# Tiva_C_Base.net
KiCad netlist of a schematic drawn in Altium Designer
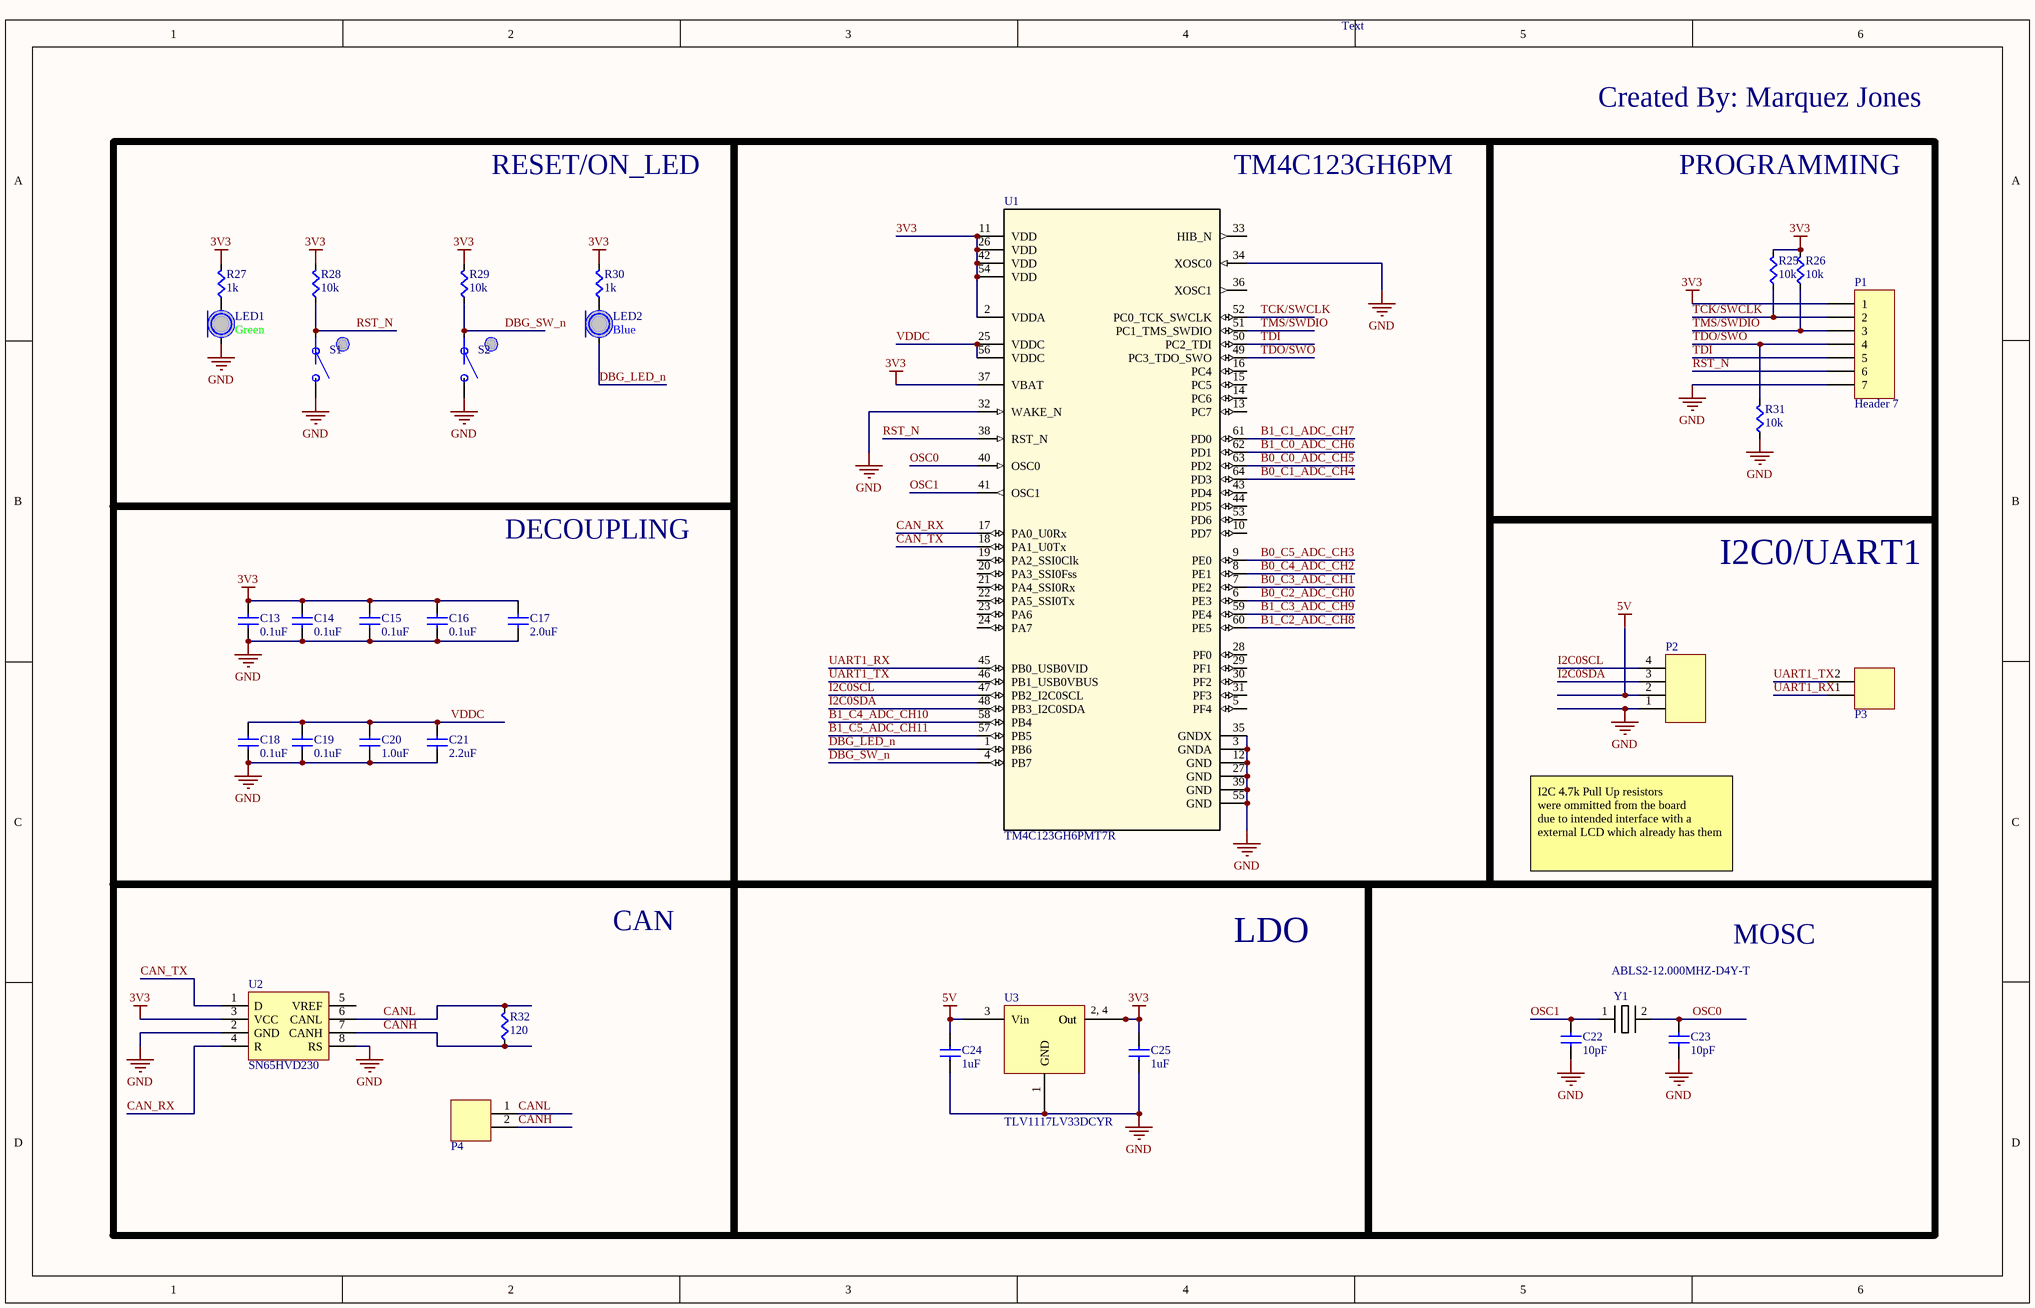
[diagram p0: Tiva_C_Base.SchDoc]

(export (version "E")
  (design (tool "Eeschema 10.0.6"))
  (components
    (comp (ref "C13")
      (value "0.1uF")
      (footprint "CAPC0603")
      (fields (field (name "Comment") "Cap"))
      (libsource (lib "SubjuGator8") (part "Cap"))
    )
    (comp (ref "C14")
      (value "0.1uF")
      (footprint "CAPC0603")
      (fields (field (name "Comment") "Cap"))
      (libsource (lib "SubjuGator8") (part "Cap"))
    )
    (comp (ref "C15")
      (value "0.1uF")
      (footprint "CAPC0603")
      (fields (field (name "Comment") "Cap"))
      (libsource (lib "SubjuGator8") (part "Cap"))
    )
    (comp (ref "C16")
      (value "0.1uF")
      (footprint "CAPC0603")
      (fields (field (name "Comment") "Cap"))
      (libsource (lib "SubjuGator8") (part "Cap"))
    )
    (comp (ref "C17")
      (value "2.0uF")
      (footprint "CAPC0603")
      (fields (field (name "Comment") "Cap"))
      (libsource (lib "SubjuGator8") (part "Cap"))
    )
    (comp (ref "C18")
      (value "0.1uF")
      (footprint "CAPC0603")
      (fields (field (name "Comment") "Cap"))
      (libsource (lib "SubjuGator8") (part "Cap"))
    )
    (comp (ref "C19")
      (value "0.1uF")
      (footprint "CAPC0603")
      (fields (field (name "Comment") "Cap"))
      (libsource (lib "SubjuGator8") (part "Cap"))
    )
    (comp (ref "C20")
      (value "1.0uF")
      (footprint "CAPC0603")
      (fields (field (name "Comment") "Cap"))
      (libsource (lib "SubjuGator8") (part "Cap"))
    )
    (comp (ref "C21")
      (value "2.2uF")
      (footprint "CAPC0603")
      (fields (field (name "Comment") "Cap"))
      (libsource (lib "SubjuGator8") (part "Cap"))
    )
    (comp (ref "C22")
      (value "10pF")
      (footprint "CAPC0603")
      (fields (field (name "Comment") "Cap"))
      (libsource (lib "Passives") (part "Cap"))
    )
    (comp (ref "C23")
      (value "10pF")
      (footprint "CAPC0603")
      (fields (field (name "Comment") "Cap"))
      (libsource (lib "Passives") (part "Cap"))
    )
    (comp (ref "C24")
      (value "1uF")
      (footprint "CAPC0603")
      (fields (field (name "MANUFACTURER PART NUMBER") "C0603C105K8PACTU") (field (name "Comment") "Cap"))
      (libsource (lib "SubjuGator8") (part "Cap"))
    )
    (comp (ref "C25")
      (value "1uF")
      (footprint "CAPC0603")
      (fields (field (name "MANUFACTURER PART NUMBER") "C0603C105K8PACTU") (field (name "Comment") "Cap"))
      (libsource (lib "SubjuGator8") (part "Cap"))
    )
    (comp (ref "LED1")
      (value "LED")
      (footprint "LED0603")
      (fields (field (name "COLOR") "Green"))
      (libsource (lib "SubjuGator8") (part "LED"))
    )
    (comp (ref "LED2")
      (value "LED")
      (footprint "LED0603")
      (fields (field (name "COLOR") "Blue"))
      (libsource (lib "SubjuGator8") (part "LED"))
    )
    (comp (ref "P1")
      (value "Header 7")
      (footprint "HDR1X7")
      (description "Header, 7-Pin")
      (fields (field (name "PUBLISHER") "Altium Limited"))
      (libsource (lib "Miscellaneous Connectors") (part "Header 7"))
    )
    (comp (ref "P2")
      (value "~")
      (footprint "MOLEX-HDR-1X4-SHERLOCK-VERT")
      (libsource (lib "SubjuGator8") (part "MOLEX-HDR-1x4-SHERLOCK_VERT"))
    )
    (comp (ref "P3")
      (value "2-pin Vert Sherlock")
      (footprint "MOLEX-HDR-1X2-SHERLOCK-VERT")
      (libsource (lib "SubjuGator8") (part "MOLEX-HDR-1x2-SHERLOCK_VERT"))
    )
    (comp (ref "P4")
      (value "2-pin Vert Sherlock")
      (footprint "MOLEX-HDR-1X2-SHERLOCK-VERT")
      (libsource (lib "") (part "MOLEX-HDR-1x2-SHERLOCK_VERT_1"))
    )
    (comp (ref "R25")
      (value "10k")
      (footprint "RES0603")
      (fields (field (name "Comment") "Res"))
      (libsource (lib "SubjuGator8") (part "Res"))
    )
    (comp (ref "R26")
      (value "10k")
      (footprint "RES0603")
      (fields (field (name "Comment") "Res"))
      (libsource (lib "SubjuGator8") (part "Res"))
    )
    (comp (ref "R27")
      (value "1k")
      (footprint "RES0603")
      (fields (field (name "Comment") "Res"))
      (libsource (lib "SubjuGator8") (part "Res"))
    )
    (comp (ref "R28")
      (value "10k")
      (footprint "RES0603")
      (fields (field (name "Comment") "Res"))
      (libsource (lib "SubjuGator8") (part "Res"))
    )
    (comp (ref "R29")
      (value "10k")
      (footprint "RES0603")
      (fields (field (name "Comment") "Res"))
      (libsource (lib "SubjuGator8") (part "Res"))
    )
    (comp (ref "R30")
      (value "1k")
      (footprint "RES0603")
      (fields (field (name "Comment") "Res"))
      (libsource (lib "SubjuGator8") (part "Res"))
    )
    (comp (ref "R31")
      (value "10k")
      (footprint "RES0603")
      (fields (field (name "Comment") "Res"))
      (libsource (lib "SubjuGator8") (part "Res"))
    )
    (comp (ref "R32")
      (value "120")
      (footprint "RES0603")
      (fields (field (name "Comment") "Res"))
      (libsource (lib "SubjuGator8") (part "Res"))
    )
    (comp (ref "S1")
      (value "Button")
      (footprint "PTS645xxxxSMTR92")
      (description "SPST Button")
      (libsource (lib "SubjuGator8") (part "Button"))
    )
    (comp (ref "S2")
      (value "Button")
      (footprint "PTS645xxxxSMTR92")
      (description "SPST Button")
      (libsource (lib "SubjuGator8") (part "Button"))
    )
    (comp (ref "U1")
      (value "TM4C123GH6PMT7R")
      (footprint "TM4C123GH6PMT7R_L")
      (description "Imported")
      (fields
        (field (name "PARTNUMBER") "TM4C123GH6PMTR")
        (field (name "ALTERNATE_PARTNUMBER") "TM4C123GH6PMT")
      )
      (libsource (lib "SubjuGator8") (part "TM4C123GH6PMT7R"))
    )
    (comp (ref "U2")
      (value "SN65HVD230")
      (footprint "SOIC-8pin")
      (description "3.3V CAN Bus Transceiver")
      (libsource (lib "SubjuGator8") (part "SN65HVD230"))
    )
    (comp (ref "U3")
      (value "TLV1117LV33DCYR")
      (footprint "SOT23-4N")
      (description "IC REG LINEAR 3.3V 1A SOT223-4")
      (fields (field (name "DIGI-KEY PART NUMBER") "296-28778-1-ND"))
      (libsource (lib "ICs") (part "TLV1117LV33DCYR"))
    )
    (comp (ref "Y1")
      (value "ABLS2-12.000MHZ-D4Y-T")
      (footprint "HC49/US")
      (description "12MHz ±30ppm Crystal 18pF 50 Ohm -40°C ~ 85°C Surface Mount HC49/US")
      (libsource (lib "SubjuGator8") (part "ABLS2-12.000MHZ-D4Y-T"))
    )
  )
  (nets
    (net (code "1") (name "/B0_C0_ADC_CH5") (class "Default")
      (node (ref "U1") (pin "63") (pinfunction "PD2_63") (pintype "bidirectional"))
    )
    (net (code "2") (name "/B0_C1_ADC_CH4") (class "Default")
      (node (ref "U1") (pin "64") (pinfunction "PD3_64") (pintype "bidirectional"))
    )
    (net (code "3") (name "/B0_C2_ADC_CH0") (class "Default")
      (node (ref "U1") (pin "6") (pinfunction "PE3_6") (pintype "bidirectional"))
    )
    (net (code "4") (name "/B0_C3_ADC_CH1") (class "Default")
      (node (ref "U1") (pin "7") (pinfunction "PE2_7") (pintype "bidirectional"))
    )
    (net (code "5") (name "/B0_C4_ADC_CH2") (class "Default")
      (node (ref "U1") (pin "8") (pinfunction "PE1_8") (pintype "bidirectional"))
    )
    (net (code "6") (name "/B0_C5_ADC_CH3") (class "Default")
      (node (ref "U1") (pin "9") (pinfunction "PE0_9") (pintype "bidirectional"))
    )
    (net (code "7") (name "/B1_C0_ADC_CH6") (class "Default")
      (node (ref "U1") (pin "62") (pinfunction "PD1_62") (pintype "bidirectional"))
    )
    (net (code "8") (name "/B1_C1_ADC_CH7") (class "Default")
      (node (ref "U1") (pin "61") (pinfunction "PD0_61") (pintype "bidirectional"))
    )
    (net (code "9") (name "/B1_C2_ADC_CH8") (class "Default")
      (node (ref "U1") (pin "60") (pinfunction "PE5_60") (pintype "bidirectional"))
    )
    (net (code "10") (name "/B1_C3_ADC_CH9") (class "Default")
      (node (ref "U1") (pin "59") (pinfunction "PE4_59") (pintype "bidirectional"))
    )
    (net (code "11") (name "/B1_C4_ADC_CH10") (class "Default")
      (node (ref "U1") (pin "58") (pinfunction "PB4_58") (pintype "bidirectional"))
    )
    (net (code "12") (name "/B1_C5_ADC_CH11") (class "Default")
      (node (ref "U1") (pin "57") (pinfunction "PB5_57") (pintype "bidirectional"))
    )
    (net (code "13") (name "/CANH") (class "Default")
      (node (ref "P4") (pin "2") (pinfunction "2_2") (pintype "passive"))
      (node (ref "R32") (pin "2") (pinfunction "B_2") (pintype "passive"))
      (node (ref "U2") (pin "7") (pinfunction "CANH_7") (pintype "passive"))
    )
    (net (code "14") (name "/CANL") (class "Default")
      (node (ref "P4") (pin "1") (pinfunction "1_1") (pintype "passive"))
      (node (ref "R32") (pin "1") (pinfunction "A_1") (pintype "passive"))
      (node (ref "U2") (pin "6") (pinfunction "CANL_6") (pintype "passive"))
    )
    (net (code "15") (name "/CAN_RX") (class "Default")
      (node (ref "U1") (pin "17") (pinfunction "PA0_U0Rx_17") (pintype "bidirectional"))
      (node (ref "U2") (pin "4") (pinfunction "R_4") (pintype "passive"))
    )
    (net (code "16") (name "/CAN_TX") (class "Default")
      (node (ref "U1") (pin "18") (pinfunction "PA1_U0Tx_18") (pintype "bidirectional"))
      (node (ref "U2") (pin "1") (pinfunction "D_1") (pintype "passive"))
    )
    (net (code "17") (name "/DBG_LED_n") (class "Default")
      (node (ref "LED2") (pin "C") (pinfunction "C_C") (pintype "passive"))
      (node (ref "U1") (pin "1") (pinfunction "PB6_1") (pintype "bidirectional"))
    )
    (net (code "18") (name "/DBG_SW_n") (class "Default")
      (node (ref "R29") (pin "2") (pinfunction "B_2") (pintype "passive"))
      (node (ref "S2") (pin "A") (pinfunction "A_A") (pintype "passive"))
      (node (ref "U1") (pin "4") (pinfunction "PB7_4") (pintype "bidirectional"))
    )
    (net (code "19") (name "/I2C0SCL") (class "Default")
      (node (ref "P2") (pin "4") (pinfunction "4_4") (pintype "passive"))
      (node (ref "U1") (pin "47") (pinfunction "PB2_I2C0SCL_47") (pintype "bidirectional"))
    )
    (net (code "20") (name "/I2C0SDA") (class "Default")
      (node (ref "P2") (pin "3") (pinfunction "3_3") (pintype "passive"))
      (node (ref "U1") (pin "48") (pinfunction "PB3_I2C0SDA_48") (pintype "bidirectional"))
    )
    (net (code "21") (name "/OSC0") (class "Default")
      (node (ref "C23") (pin "1") (pinfunction "A_1") (pintype "passive"))
      (node (ref "U1") (pin "40") (pinfunction "OSC0_40") (pintype "input"))
      (node (ref "Y1") (pin "2") (pinfunction "2_2") (pintype "passive"))
    )
    (net (code "22") (name "/OSC1") (class "Default")
      (node (ref "C22") (pin "1") (pinfunction "A_1") (pintype "passive"))
      (node (ref "U1") (pin "41") (pinfunction "OSC1_41") (pintype "output"))
      (node (ref "Y1") (pin "1") (pinfunction "1_1") (pintype "passive"))
    )
    (net (code "23") (name "/RST_N") (class "Default")
      (node (ref "P1") (pin "6") (pinfunction "6_6") (pintype "passive"))
      (node (ref "R28") (pin "2") (pinfunction "B_2") (pintype "passive"))
      (node (ref "S1") (pin "A") (pinfunction "A_A") (pintype "passive"))
      (node (ref "U1") (pin "38") (pinfunction "RST_N_38") (pintype "input"))
    )
    (net (code "24") (name "/TCK{slash}SWCLK") (class "Default")
      (node (ref "P1") (pin "2") (pinfunction "2_2") (pintype "passive"))
      (node (ref "R25") (pin "2") (pinfunction "B_2") (pintype "passive"))
      (node (ref "U1") (pin "52") (pinfunction "PC0_TCK_SWCLK_52") (pintype "bidirectional"))
    )
    (net (code "25") (name "/TDI") (class "Default")
      (node (ref "P1") (pin "5") (pinfunction "5_5") (pintype "passive"))
      (node (ref "U1") (pin "50") (pinfunction "PC2_TDI_50") (pintype "bidirectional"))
    )
    (net (code "26") (name "/TDO{slash}SWO") (class "Default")
      (node (ref "P1") (pin "4") (pinfunction "4_4") (pintype "passive"))
      (node (ref "R31") (pin "1") (pinfunction "A_1") (pintype "passive"))
      (node (ref "U1") (pin "49") (pinfunction "PC3_TDO_SWO_49") (pintype "bidirectional"))
    )
    (net (code "27") (name "/TMS{slash}SWDIO") (class "Default")
      (node (ref "P1") (pin "3") (pinfunction "3_3") (pintype "passive"))
      (node (ref "R26") (pin "2") (pinfunction "B_2") (pintype "passive"))
      (node (ref "U1") (pin "51") (pinfunction "PC1_TMS_SWDIO_51") (pintype "bidirectional"))
    )
    (net (code "28") (name "/UART1_RX") (class "Default")
      (node (ref "P3") (pin "1") (pinfunction "1_1") (pintype "passive"))
      (node (ref "U1") (pin "45") (pinfunction "PB0_USB0VID_45") (pintype "bidirectional"))
    )
    (net (code "29") (name "/UART1_TX") (class "Default")
      (node (ref "P3") (pin "2") (pinfunction "2_2") (pintype "passive"))
      (node (ref "U1") (pin "46") (pinfunction "PB1_USB0VBUS_46") (pintype "bidirectional"))
    )
    (net (code "30") (name "/VDDC") (class "Default")
      (node (ref "C18") (pin "1") (pinfunction "A_1") (pintype "passive"))
      (node (ref "C19") (pin "1") (pinfunction "A_1") (pintype "passive"))
      (node (ref "C20") (pin "1") (pinfunction "A_1") (pintype "passive"))
      (node (ref "C21") (pin "1") (pinfunction "A_1") (pintype "passive"))
      (node (ref "U1") (pin "25") (pinfunction "VDDC_25") (pintype "power_in"))
      (node (ref "U1") (pin "56") (pinfunction "VDDC_56") (pintype "power_in"))
    )
    (net (code "31") (name "3V3") (class "Default")
      (node (ref "C13") (pin "1") (pinfunction "A_1") (pintype "passive"))
      (node (ref "C14") (pin "1") (pinfunction "A_1") (pintype "passive"))
      (node (ref "C15") (pin "1") (pinfunction "A_1") (pintype "passive"))
      (node (ref "C16") (pin "1") (pinfunction "A_1") (pintype "passive"))
      (node (ref "C17") (pin "1") (pinfunction "A_1") (pintype "passive"))
      (node (ref "C25") (pin "1") (pinfunction "A_1") (pintype "passive"))
      (node (ref "P1") (pin "1") (pinfunction "1_1") (pintype "passive"))
      (node (ref "R25") (pin "1") (pinfunction "A_1") (pintype "passive"))
      (node (ref "R26") (pin "1") (pinfunction "A_1") (pintype "passive"))
      (node (ref "R27") (pin "1") (pinfunction "A_1") (pintype "passive"))
      (node (ref "R28") (pin "1") (pinfunction "A_1") (pintype "passive"))
      (node (ref "R29") (pin "1") (pinfunction "A_1") (pintype "passive"))
      (node (ref "R30") (pin "1") (pinfunction "A_1") (pintype "passive"))
      (node (ref "U1") (pin "11") (pinfunction "VDD_11") (pintype "power_in"))
      (node (ref "U1") (pin "2") (pinfunction "VDDA_2") (pintype "power_in"))
      (node (ref "U1") (pin "26") (pinfunction "VDD_26") (pintype "power_in"))
      (node (ref "U1") (pin "37") (pinfunction "VBAT_37") (pintype "power_in"))
      (node (ref "U1") (pin "42") (pinfunction "VDD_42") (pintype "power_in"))
      (node (ref "U1") (pin "54") (pinfunction "VDD_54") (pintype "power_in"))
      (node (ref "U2") (pin "3") (pinfunction "VCC_3") (pintype "passive"))
      (node (ref "U3") (pin "2") (pinfunction "Out_2") (pintype "passive"))
      (node (ref "U3") (pin "4") (pinfunction "Out_4") (pintype "passive"))
    )
    (net (code "32") (name "5V") (class "Default")
      (node (ref "C24") (pin "1") (pinfunction "A_1") (pintype "passive"))
      (node (ref "P2") (pin "2") (pinfunction "2_2") (pintype "passive"))
      (node (ref "U3") (pin "3") (pinfunction "Vin_3") (pintype "passive"))
    )
    (net (code "33") (name "GND") (class "Default")
      (node (ref "C13") (pin "2") (pinfunction "B_2") (pintype "passive"))
      (node (ref "C14") (pin "2") (pinfunction "B_2") (pintype "passive"))
      (node (ref "C15") (pin "2") (pinfunction "B_2") (pintype "passive"))
      (node (ref "C16") (pin "2") (pinfunction "B_2") (pintype "passive"))
      (node (ref "C17") (pin "2") (pinfunction "B_2") (pintype "passive"))
      (node (ref "C18") (pin "2") (pinfunction "B_2") (pintype "passive"))
      (node (ref "C19") (pin "2") (pinfunction "B_2") (pintype "passive"))
      (node (ref "C20") (pin "2") (pinfunction "B_2") (pintype "passive"))
      (node (ref "C21") (pin "2") (pinfunction "B_2") (pintype "passive"))
      (node (ref "C22") (pin "2") (pinfunction "B_2") (pintype "passive"))
      (node (ref "C23") (pin "2") (pinfunction "B_2") (pintype "passive"))
      (node (ref "C24") (pin "2") (pinfunction "B_2") (pintype "passive"))
      (node (ref "C25") (pin "2") (pinfunction "B_2") (pintype "passive"))
      (node (ref "LED1") (pin "C") (pinfunction "C_C") (pintype "passive"))
      (node (ref "P1") (pin "7") (pinfunction "7_7") (pintype "passive"))
      (node (ref "P2") (pin "1") (pinfunction "1_1") (pintype "passive"))
      (node (ref "R31") (pin "2") (pinfunction "B_2") (pintype "passive"))
      (node (ref "S1") (pin "B") (pinfunction "B_B") (pintype "passive"))
      (node (ref "S2") (pin "B") (pinfunction "B_B") (pintype "passive"))
      (node (ref "U1") (pin "12") (pinfunction "GND_12") (pintype "power_in"))
      (node (ref "U1") (pin "27") (pinfunction "GND_27") (pintype "power_in"))
      (node (ref "U1") (pin "3") (pinfunction "GNDA_3") (pintype "power_in"))
      (node (ref "U1") (pin "32") (pinfunction "WAKE_N_32") (pintype "input"))
      (node (ref "U1") (pin "34") (pinfunction "XOSC0_34") (pintype "input"))
      (node (ref "U1") (pin "35") (pinfunction "GNDX_35") (pintype "power_in"))
      (node (ref "U1") (pin "39") (pinfunction "GND_39") (pintype "power_in"))
      (node (ref "U1") (pin "55") (pinfunction "GND_55") (pintype "power_in"))
      (node (ref "U2") (pin "2") (pinfunction "GND_2") (pintype "passive"))
      (node (ref "U2") (pin "8") (pinfunction "RS_8") (pintype "passive"))
      (node (ref "U3") (pin "1") (pinfunction "GND_1") (pintype "passive"))
    )
    (net (code "34") (name "Net-(R27-B)") (class "Default")
      (node (ref "LED1") (pin "A") (pinfunction "A_A") (pintype "passive"))
      (node (ref "R27") (pin "2") (pinfunction "B_2") (pintype "passive"))
    )
    (net (code "35") (name "Net-(R30-B)") (class "Default")
      (node (ref "LED2") (pin "A") (pinfunction "A_A") (pintype "passive"))
      (node (ref "R30") (pin "2") (pinfunction "B_2") (pintype "passive"))
    )
    (net (code "36") (name "unconnected-(U1-HIB_N-Pad33)") (class "Default")
      (node (ref "U1") (pin "33") (pinfunction "HIB_N_33") (pintype "output"))
    )
    (net (code "37") (name "unconnected-(U1-PA2_SSI0Clk-Pad19)") (class "Default")
      (node (ref "U1") (pin "19") (pinfunction "PA2_SSI0Clk_19") (pintype "bidirectional"))
    )
    (net (code "38") (name "unconnected-(U1-PA3_SSI0Fss-Pad20)") (class "Default")
      (node (ref "U1") (pin "20") (pinfunction "PA3_SSI0Fss_20") (pintype "bidirectional"))
    )
    (net (code "39") (name "unconnected-(U1-PA4_SSI0Rx-Pad21)") (class "Default")
      (node (ref "U1") (pin "21") (pinfunction "PA4_SSI0Rx_21") (pintype "bidirectional"))
    )
    (net (code "40") (name "unconnected-(U1-PA5_SSI0Tx-Pad22)") (class "Default")
      (node (ref "U1") (pin "22") (pinfunction "PA5_SSI0Tx_22") (pintype "bidirectional"))
    )
    (net (code "41") (name "unconnected-(U1-PA6-Pad23)") (class "Default")
      (node (ref "U1") (pin "23") (pinfunction "PA6_23") (pintype "bidirectional"))
    )
    (net (code "42") (name "unconnected-(U1-PA7-Pad24)") (class "Default")
      (node (ref "U1") (pin "24") (pinfunction "PA7_24") (pintype "bidirectional"))
    )
    (net (code "43") (name "unconnected-(U1-PC4-Pad16)") (class "Default")
      (node (ref "U1") (pin "16") (pinfunction "PC4_16") (pintype "bidirectional"))
    )
    (net (code "44") (name "unconnected-(U1-PC5-Pad15)") (class "Default")
      (node (ref "U1") (pin "15") (pinfunction "PC5_15") (pintype "bidirectional"))
    )
    (net (code "45") (name "unconnected-(U1-PC6-Pad14)") (class "Default")
      (node (ref "U1") (pin "14") (pinfunction "PC6_14") (pintype "bidirectional"))
    )
    (net (code "46") (name "unconnected-(U1-PC7-Pad13)") (class "Default")
      (node (ref "U1") (pin "13") (pinfunction "PC7_13") (pintype "bidirectional"))
    )
    (net (code "47") (name "unconnected-(U1-PD4-Pad43)") (class "Default")
      (node (ref "U1") (pin "43") (pinfunction "PD4_43") (pintype "bidirectional"))
    )
    (net (code "48") (name "unconnected-(U1-PD5-Pad44)") (class "Default")
      (node (ref "U1") (pin "44") (pinfunction "PD5_44") (pintype "bidirectional"))
    )
    (net (code "49") (name "unconnected-(U1-PD6-Pad53)") (class "Default")
      (node (ref "U1") (pin "53") (pinfunction "PD6_53") (pintype "bidirectional"))
    )
    (net (code "50") (name "unconnected-(U1-PD7-Pad10)") (class "Default")
      (node (ref "U1") (pin "10") (pinfunction "PD7_10") (pintype "bidirectional"))
    )
    (net (code "51") (name "unconnected-(U1-PF0-Pad28)") (class "Default")
      (node (ref "U1") (pin "28") (pinfunction "PF0_28") (pintype "bidirectional"))
    )
    (net (code "52") (name "unconnected-(U1-PF1-Pad29)") (class "Default")
      (node (ref "U1") (pin "29") (pinfunction "PF1_29") (pintype "bidirectional"))
    )
    (net (code "53") (name "unconnected-(U1-PF2-Pad30)") (class "Default")
      (node (ref "U1") (pin "30") (pinfunction "PF2_30") (pintype "bidirectional"))
    )
    (net (code "54") (name "unconnected-(U1-PF3-Pad31)") (class "Default")
      (node (ref "U1") (pin "31") (pinfunction "PF3_31") (pintype "bidirectional"))
    )
    (net (code "55") (name "unconnected-(U1-PF4-Pad5)") (class "Default")
      (node (ref "U1") (pin "5") (pinfunction "PF4_5") (pintype "bidirectional"))
    )
    (net (code "56") (name "unconnected-(U1-XOSC1-Pad36)") (class "Default")
      (node (ref "U1") (pin "36") (pinfunction "XOSC1_36") (pintype "output"))
    )
    (net (code "57") (name "unconnected-(U2-VREF-Pad5)") (class "Default")
      (node (ref "U2") (pin "5") (pinfunction "VREF_5") (pintype "passive"))
    )
  )
)
